# FPGA_Config.net
KiCad netlist of a schematic drawn in Altium Designer
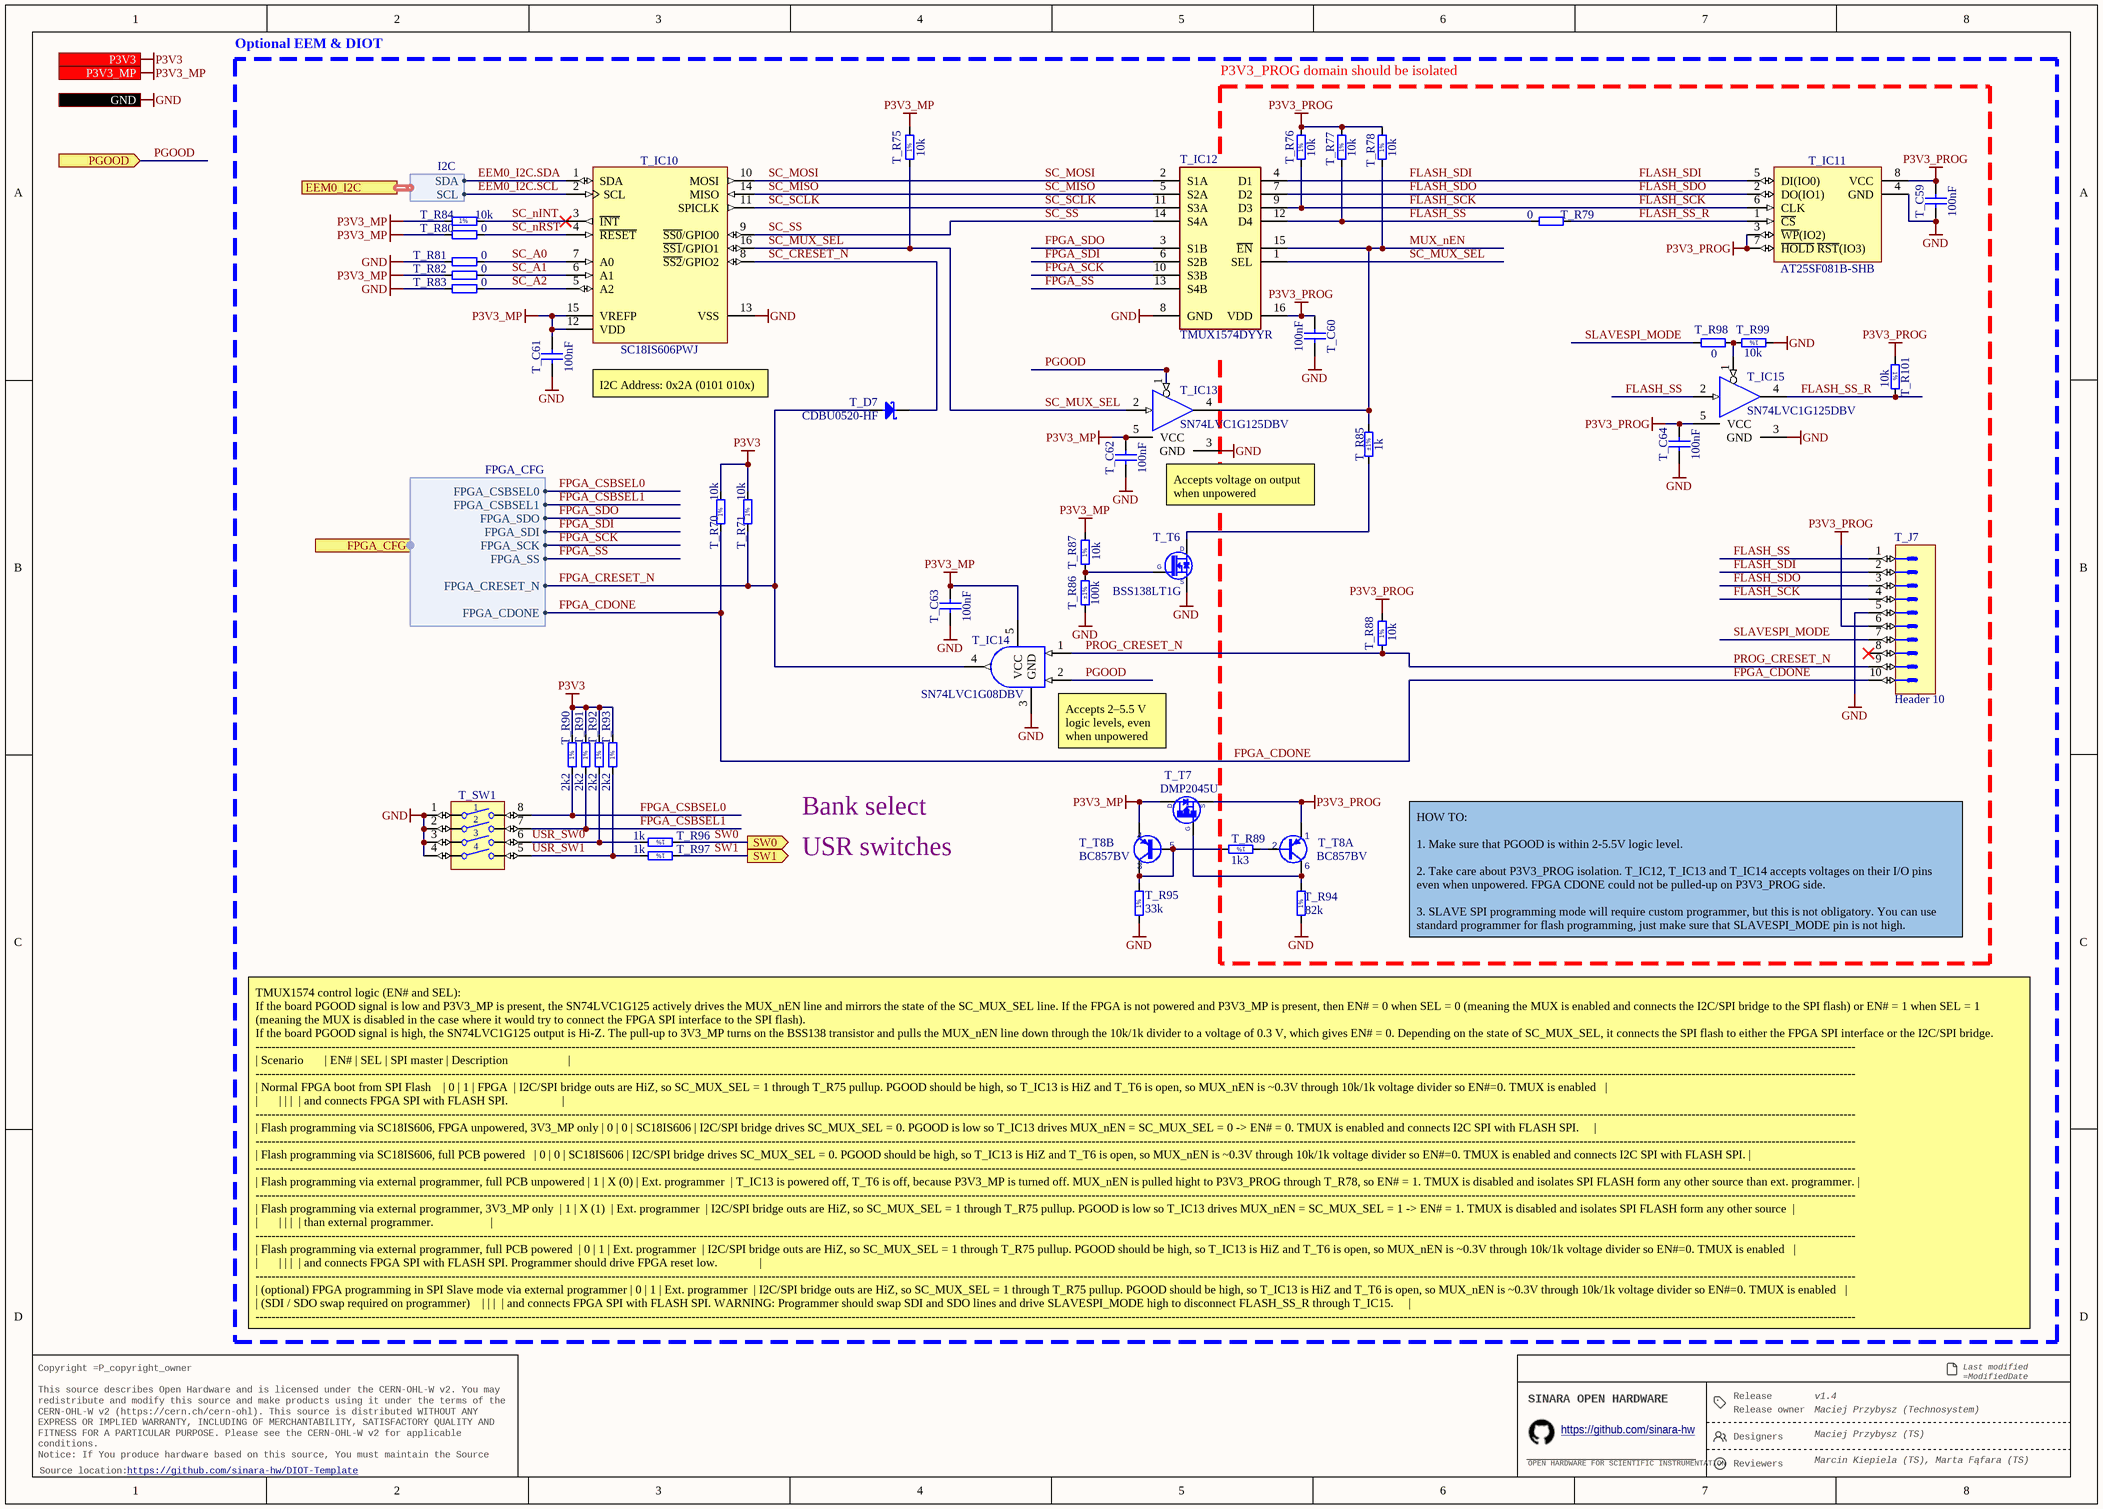
[diagram p0: FPGA_Config.SchDoc]

(export (version "E")
  (design (tool "Eeschema 10.0.6"))
  (components
    (comp (ref "T_C59")
      (value "100nF")
      (footprint "CAPC1005X55N")
      (description "Non-polarised capacitor")
      (fields
        (field (name "PART NUMBER") "CC0402_100NF_50V_10%_X7R")
        (field (name "VOLTAGE") "50V")
        (field (name "AUTHOR") "CERN DEM MR")
      )
      (libsource (lib "Capacitors") (part "Capacitor - non polarized"))
    )
    (comp (ref "T_C60")
      (value "100nF")
      (footprint "CAPC1005X55N")
      (description "Non-polarised capacitor")
      (fields
        (field (name "PART NUMBER") "CC0402_100NF_50V_10%_X7R")
        (field (name "VOLTAGE") "50V")
        (field (name "AUTHOR") "CERN DEM MR")
      )
      (libsource (lib "Capacitors") (part "Capacitor - non polarized"))
    )
    (comp (ref "T_C61")
      (value "100nF")
      (footprint "CAPC1005X55N")
      (description "Non-polarised capacitor")
      (fields
        (field (name "PART NUMBER") "CC0402_100NF_50V_10%_X7R")
        (field (name "VOLTAGE") "50V")
        (field (name "AUTHOR") "CERN DEM MR")
      )
      (libsource (lib "Capacitors") (part "Capacitor - non polarized"))
    )
    (comp (ref "T_C62")
      (value "100nF")
      (footprint "CAPC1005X55N")
      (description "Non-polarised capacitor")
      (fields
        (field (name "PART NUMBER") "CC0402_100NF_50V_10%_X7R")
        (field (name "VOLTAGE") "50V")
        (field (name "AUTHOR") "CERN DEM MR")
      )
      (libsource (lib "Capacitors") (part "Capacitor - non polarized"))
    )
    (comp (ref "T_C63")
      (value "100nF")
      (footprint "CAPC1005X55N")
      (description "Non-polarised capacitor")
      (fields
        (field (name "PART NUMBER") "CC0402_100NF_50V_10%_X7R")
        (field (name "VOLTAGE") "50V")
        (field (name "AUTHOR") "CERN DEM MR")
      )
      (libsource (lib "Capacitors") (part "Capacitor - non polarized"))
    )
    (comp (ref "T_C64")
      (value "100nF")
      (footprint "CAPC1005X55N")
      (description "Non-polarised capacitor")
      (fields
        (field (name "PART NUMBER") "CC0402_100NF_50V_10%_X7R")
        (field (name "VOLTAGE") "50V")
        (field (name "AUTHOR") "CERN DEM MR")
      )
      (libsource (lib "Capacitors") (part "Capacitor - non polarized"))
    )
    (comp (ref "T_D7")
      (value "CDBU0520-HF")
      (footprint "SOD-523F")
      (description "Schottky Diode")
      (fields
        (field (name "VOLTAGE") "20V")
        (field (name "POWER") "500mA")
        (field (name "AUTHOR") "CERN DEM HF")
      )
      (libsource (lib "ICs And Semiconductors") (part "Diode Schottky"))
    )
    (comp (ref "T_IC10")
      (value "SC18IS606PWJ")
      (footprint "SOP65P640X110-16N")
      (description "I2C-bus to SPI bridge")
      (fields (field (name "MANUFACTURER") "NXP SEMICONDUCTORS") (field (name "AUTHOR") "GK"))
      (libsource (lib "ICS-logic") (part "SC18IS606PWJ"))
    )
    (comp (ref "T_IC11")
      (value "AT25SF081B-SHB")
      (footprint "SOIC127P790X216-8N")
      (description "8M-bit Serial Flash Memory with uniform 4KB sectors and Dual/Quad SPI and QPI")
      (fields (field (name "MANUFACTURER") "Renesas") (field (name "AUTHOR") "GK"))
      (libsource (lib "ICS-logic") (part "MEM_AT25SF081B-SHB"))
    )
    (comp (ref "T_IC12")
      (value "TMUX1574DYYR")
      (footprint "SamacSys:SOP50P326X110-16N")
      (description "Integrated Circuit")
      (fields (field (name "MOUSER PART NUMBER") "595-TMUX1574DYYR"))
      (libsource (lib "SamacSys") (part "TMUX1574DYYR"))
    )
    (comp (ref "T_IC13")
      (value "SN74LVC1G125DBV")
      (footprint "SOT95P280X145-5N")
      (description "Single Bus Buffer Gate With 3-State Output")
      (fields (field (name "MANUFACTURER") "TEXAS INSTRUMENTS") (field (name "AUTHOR") "CERN DEM HF"))
      (libsource (lib "ICs And Semiconductors") (part "741G125"))
    )
    (comp (ref "T_IC14")
      (value "SN74LVC1G08DBV")
      (footprint "SOT95P280X145-5N")
      (description "Single 2-Input AND Gate")
      (fields (field (name "MANUFACTURER") "TEXAS INSTRUMENTS") (field (name "AUTHOR") "CERN DEM JLC"))
      (libsource (lib "ICs And Semiconductors") (part "741G08"))
    )
    (comp (ref "T_IC15")
      (value "SN74LVC1G125DBV")
      (footprint "SOT95P280X145-5N")
      (description "Single Bus Buffer Gate With 3-State Output")
      (fields (field (name "MANUFACTURER") "TEXAS INSTRUMENTS") (field (name "AUTHOR") "CERN DEM HF"))
      (libsource (lib "ICs And Semiconductors") (part "741G125"))
    )
    (comp (ref "T_J7")
      (value "Header 10")
      (footprint "HARWIN_M20-9980546")
      (description "Connector 10 Male")
      (fields
        (field (name "PART NUMBER") "HARWIN_M20-9980546")
        (field (name "MANUFACTURER") "HARWIN")
        (field (name "AUTHOR") "CERN DEM MR")
      )
      (libsource (lib "Connectors") (part "Connector 10 Male"))
    )
    (comp (ref "T_R70")
      (value "10k")
      (footprint "RESC1005X40N")
      (description "Resistor - 1%")
      (fields
        (field (name "PART NUMBER") "R0402_10K_1%_0.0625W_100PPM")
        (field (name "POWER") "0.0625W")
        (field (name "AUTHOR") "CERN DEM JLC")
      )
      (libsource (lib "Resistors") (part "Resistor - 1%"))
    )
    (comp (ref "T_R71")
      (value "10k")
      (footprint "RESC1005X40N")
      (description "Resistor - 1%")
      (fields
        (field (name "PART NUMBER") "R0402_10K_1%_0.0625W_100PPM")
        (field (name "POWER") "0.0625W")
        (field (name "AUTHOR") "CERN DEM JLC")
      )
      (libsource (lib "Resistors") (part "Resistor - 1%"))
    )
    (comp (ref "T_R75")
      (value "10k")
      (footprint "RESC1005X40N")
      (description "Resistor - 1%")
      (fields
        (field (name "PART NUMBER") "R0402_10K_1%_0.0625W_100PPM")
        (field (name "POWER") "0.0625W")
        (field (name "AUTHOR") "CERN DEM JLC")
      )
      (libsource (lib "Resistors") (part "Resistor - 1%"))
    )
    (comp (ref "T_R76")
      (value "10k")
      (footprint "RESC1005X40N")
      (description "Resistor - 1%")
      (fields
        (field (name "PART NUMBER") "R0402_10K_1%_0.0625W_100PPM")
        (field (name "POWER") "0.0625W")
        (field (name "AUTHOR") "CERN DEM JLC")
      )
      (libsource (lib "Resistors") (part "Resistor - 1%"))
    )
    (comp (ref "T_R77")
      (value "10k")
      (footprint "RESC1005X40N")
      (description "Resistor - 1%")
      (fields
        (field (name "PART NUMBER") "R0402_10K_1%_0.0625W_100PPM")
        (field (name "POWER") "0.0625W")
        (field (name "AUTHOR") "CERN DEM JLC")
      )
      (libsource (lib "Resistors") (part "Resistor - 1%"))
    )
    (comp (ref "T_R78")
      (value "10k")
      (footprint "RESC1005X40N")
      (description "Resistor - 1%")
      (fields
        (field (name "PART NUMBER") "R0402_10K_1%_0.0625W_100PPM")
        (field (name "POWER") "0.0625W")
        (field (name "AUTHOR") "CERN DEM JLC")
      )
      (libsource (lib "Resistors") (part "Resistor - 1%"))
    )
    (comp (ref "T_R79")
      (value "0")
      (footprint "RESC1005X40N")
      (description "Resistor")
      (fields
        (field (name "PART NUMBER") "R0402_0R_JUMPER")
        (field (name "MANUFACTURER") "GENERIC")
        (field (name "AUTHOR") "CERN DEM JLC")
      )
      (libsource (lib "Resistors") (part "Resistor"))
    )
    (comp (ref "T_R80")
      (value "0")
      (footprint "RESC1005X40N")
      (description "Resistor")
      (fields
        (field (name "PART NUMBER") "R0402_0R_JUMPER")
        (field (name "MANUFACTURER") "GENERIC")
        (field (name "AUTHOR") "CERN DEM JLC")
      )
      (libsource (lib "Resistors") (part "Resistor"))
    )
    (comp (ref "T_R81")
      (value "0")
      (footprint "RESC1005X40N")
      (description "Resistor")
      (fields
        (field (name "PART NUMBER") "R0402_0R_JUMPER")
        (field (name "MANUFACTURER") "GENERIC")
        (field (name "AUTHOR") "CERN DEM JLC")
      )
      (libsource (lib "Resistors") (part "Resistor"))
    )
    (comp (ref "T_R82")
      (value "0")
      (footprint "RESC1005X40N")
      (description "Resistor")
      (fields
        (field (name "PART NUMBER") "R0402_0R_JUMPER")
        (field (name "MANUFACTURER") "GENERIC")
        (field (name "AUTHOR") "CERN DEM JLC")
      )
      (libsource (lib "Resistors") (part "Resistor"))
    )
    (comp (ref "T_R83")
      (value "0")
      (footprint "RESC1005X40N")
      (description "Resistor")
      (fields
        (field (name "PART NUMBER") "R0402_0R_JUMPER")
        (field (name "MANUFACTURER") "GENERIC")
        (field (name "AUTHOR") "CERN DEM JLC")
      )
      (libsource (lib "Resistors") (part "Resistor"))
    )
    (comp (ref "T_R84")
      (value "10k")
      (footprint "RESC1005X40N")
      (description "Resistor - 1%")
      (fields
        (field (name "PART NUMBER") "R0402_10K_1%_0.0625W_100PPM")
        (field (name "POWER") "0.0625W")
        (field (name "AUTHOR") "CERN DEM JLC")
      )
      (libsource (lib "Resistors") (part "Resistor - 1%"))
    )
    (comp (ref "T_R85")
      (value "1k")
      (footprint "RESC1005X40N")
      (description "Resistor - 1%")
      (fields
        (field (name "TOLERANCE") "±1%")
        (field (name "PART NUMBER") "R0402_1K_1%_0.0625W_100PPM")
        (field (name "POWER") "0.0625W")
        (field (name "AUTHOR") "CERN DEM JLC")
      )
      (libsource (lib "Resistors") (part "Resistor - 1%"))
    )
    (comp (ref "T_R86")
      (value "100k")
      (footprint "RESC1005X40N")
      (description "Resistor - 1%")
      (fields
        (field (name "TOLERANCE") "±1%")
        (field (name "PART NUMBER") "R0402_100K_1%_0.0625W_100PPM")
        (field (name "POWER") "0.0625W")
        (field (name "AUTHOR") "CERN DEM JLC")
      )
      (libsource (lib "Resistors") (part "Resistor - 1%"))
    )
    (comp (ref "T_R87")
      (value "10k")
      (footprint "RESC1005X40N")
      (description "Resistor - 1%")
      (fields
        (field (name "PART NUMBER") "R0402_10K_1%_0.0625W_100PPM")
        (field (name "POWER") "0.0625W")
        (field (name "AUTHOR") "CERN DEM JLC")
      )
      (libsource (lib "Resistors") (part "Resistor - 1%"))
    )
    (comp (ref "T_R88")
      (value "10k")
      (footprint "RESC1005X40N")
      (description "Resistor - 1%")
      (fields
        (field (name "PART NUMBER") "R0402_10K_1%_0.0625W_100PPM")
        (field (name "POWER") "0.0625W")
        (field (name "AUTHOR") "CERN DEM JLC")
      )
      (libsource (lib "Resistors") (part "Resistor - 1%"))
    )
    (comp (ref "T_R89")
      (value "1k3")
      (footprint "RESC1608X55N")
      (description "Resistor - 1%")
      (fields
        (field (name "PART NUMBER") "R0603_1K3_1%_0.1W_100PPM")
        (field (name "POWER") "0.1W")
        (field (name "AUTHOR") "CERN DEM JLC")
      )
      (libsource (lib "Resistors") (part "Resistor - 1%"))
    )
    (comp (ref "T_R90")
      (value "2k2")
      (footprint "RESC1005X40N")
      (description "Resistor - 1%")
      (fields
        (field (name "PART NUMBER") "R0402_2K2_1%_0.0625W_100PPM")
        (field (name "POWER") "0.0625W")
        (field (name "AUTHOR") "CERN DEM JLC")
      )
      (libsource (lib "Resistors") (part "Resistor - 1%"))
    )
    (comp (ref "T_R91")
      (value "2k2")
      (footprint "RESC1005X40N")
      (description "Resistor - 1%")
      (fields
        (field (name "PART NUMBER") "R0402_2K2_1%_0.0625W_100PPM")
        (field (name "POWER") "0.0625W")
        (field (name "AUTHOR") "CERN DEM JLC")
      )
      (libsource (lib "Resistors") (part "Resistor - 1%"))
    )
    (comp (ref "T_R92")
      (value "2k2")
      (footprint "RESC1005X40N")
      (description "Resistor - 1%")
      (fields
        (field (name "PART NUMBER") "R0402_2K2_1%_0.0625W_100PPM")
        (field (name "POWER") "0.0625W")
        (field (name "AUTHOR") "CERN DEM JLC")
      )
      (libsource (lib "Resistors") (part "Resistor - 1%"))
    )
    (comp (ref "T_R93")
      (value "2k2")
      (footprint "RESC1005X40N")
      (description "Resistor - 1%")
      (fields
        (field (name "PART NUMBER") "R0402_2K2_1%_0.0625W_100PPM")
        (field (name "POWER") "0.0625W")
        (field (name "AUTHOR") "CERN DEM JLC")
      )
      (libsource (lib "Resistors") (part "Resistor - 1%"))
    )
    (comp (ref "T_R94")
      (value "82k")
      (footprint "RESC1608X55N")
      (description "Resistor - 1%")
      (fields
        (field (name "PART NUMBER") "R0603_82K_1%_0.1W_100PPM")
        (field (name "POWER") "0.1W")
        (field (name "AUTHOR") "CERN DEM JLC")
      )
      (libsource (lib "Resistors") (part "Resistor - 1%"))
    )
    (comp (ref "T_R95")
      (value "33k")
      (footprint "RESC1005X40N")
      (description "Resistor - 1%")
      (fields
        (field (name "PART NUMBER") "R0402_33K_1%_0.0625W_100PPM")
        (field (name "POWER") "0.0625W")
        (field (name "AUTHOR") "CERN DEM JLC")
      )
      (libsource (lib "Resistors") (part "Resistor - 1%"))
    )
    (comp (ref "T_R96")
      (value "1k")
      (footprint "RESC1005X40N")
      (description "Resistor - 1%")
      (fields
        (field (name "PART NUMBER") "R0402_1K_1%_0.0625W_100PPM")
        (field (name "POWER") "0.0625W")
        (field (name "AUTHOR") "CERN DEM JLC")
      )
      (libsource (lib "Resistors") (part "Resistor - 1%"))
    )
    (comp (ref "T_R97")
      (value "1k")
      (footprint "RESC1005X40N")
      (description "Resistor - 1%")
      (fields
        (field (name "PART NUMBER") "R0402_1K_1%_0.0625W_100PPM")
        (field (name "POWER") "0.0625W")
        (field (name "AUTHOR") "CERN DEM JLC")
      )
      (libsource (lib "Resistors") (part "Resistor - 1%"))
    )
    (comp (ref "T_R98")
      (value "0")
      (footprint "RESC1005X40N")
      (description "Resistor")
      (fields
        (field (name "PART NUMBER") "R0402_0R_JUMPER")
        (field (name "MANUFACTURER") "GENERIC")
        (field (name "AUTHOR") "CERN DEM JLC")
      )
      (libsource (lib "Resistors") (part "Resistor"))
    )
    (comp (ref "T_R99")
      (value "10k")
      (footprint "RESC1005X40N")
      (description "Resistor - 1%")
      (fields
        (field (name "PART NUMBER") "R0402_10K_1%_0.0625W_100PPM")
        (field (name "POWER") "0.0625W")
        (field (name "AUTHOR") "CERN DEM JLC")
      )
      (libsource (lib "Resistors") (part "Resistor - 1%"))
    )
    (comp (ref "T_R101")
      (value "10k")
      (footprint "RESC1005X40N")
      (description "Resistor - 1%")
      (fields
        (field (name "PART NUMBER") "R0402_10K_1%_0.0625W_100PPM")
        (field (name "POWER") "0.0625W")
        (field (name "AUTHOR") "CERN DEM JLC")
      )
      (libsource (lib "Resistors") (part "Resistor - 1%"))
    )
    (comp (ref "T_SW1")
      (value "Switch")
      (footprint "SW_TYCO_1571983-4")
      (description "4 Ways SPST DIP Switch")
      (fields
        (field (name "PART NUMBER") "SW_TYCO_1571983-4")
        (field (name "MANUFACTURER") "TYCO")
        (field (name "AUTHOR") "CERN DEM JLC")
      )
      (libsource (lib "Eletro-mechanical") (part "SW 4x SPST DIP Switch"))
    )
    (comp (ref "T_T6")
      (value "BSS138LT1G")
      (footprint "SOT95P240X110-3N")
      (description "N-CHANNEL MOSFET WITH DIODE")
      (fields
        (field (name "MANUFACTURER") "ON SEMICONDUCTOR")
        (field (name "MANUFACTURER PART NUMBER") "BSS138L")
        (field (name "AUTHOR") "CERN DEM JLC")
      )
      (libsource (lib "ICs And Semiconductors") (part "N-MOSFET-D 1G 2S 3D"))
    )
    (comp (ref "T_T7")
      (value "DMP2045U")
      (footprint "SOT95P240X110-3N")
      (description "P-CHANNEL MOSFET WITH DIODE")
      (fields (field (name "MANUFACTURER") "DIODES INCORPORATED") (field (name "AUTHOR") "CERN DEM HF"))
      (libsource (lib "ICs And Semiconductors") (part "P-MOSFET-D 1G 2S 3D"))
    )
    (comp (ref "T_T8")
      (value "BC857BV")
      (footprint "SOTFL50P160X60-6N")
      (description "45V, 100mA PNP General Purpose Double Transistor")
      (fields (field (name "MANUFACTURER") "NXP SEMICONDUCTORS") (field (name "AUTHOR") "CERN DEM JLC"))
      (libsource (lib "ICs And Semiconductors") (part "BC857BV"))
    )
  )
  (nets
    (net (code "3") (name "/EEM0_I2C.SCL") (class "Default")
      (node (ref "T_IC10") (pin "2") (pinfunction "SCL_2") (pintype "input"))
    )
    (net (code "4") (name "/EEM0_I2C.SDA") (class "Default")
      (node (ref "T_IC10") (pin "1") (pinfunction "SDA_1") (pintype "bidirectional"))
    )
    (net (code "5") (name "/FLASH_SCK") (class "Default")
      (node (ref "T_IC11") (pin "6") (pinfunction "CLK_6") (pintype "input"))
      (node (ref "T_IC12") (pin "9") (pinfunction "D3_9") (pintype "passive"))
      (node (ref "T_J7") (pin "4") (pinfunction "4_4") (pintype "bidirectional"))
      (node (ref "T_R76") (pin "1") (pinfunction "1_1") (pintype "passive"))
    )
    (net (code "6") (name "/FLASH_SDI") (class "Default")
      (node (ref "T_IC11") (pin "5") (pinfunction "DI(IO0)_5") (pintype "bidirectional"))
      (node (ref "T_IC12") (pin "4") (pinfunction "D1_4") (pintype "passive"))
      (node (ref "T_J7") (pin "2") (pinfunction "2_2") (pintype "bidirectional"))
    )
    (net (code "7") (name "/FLASH_SDO") (class "Default")
      (node (ref "T_IC11") (pin "2") (pinfunction "DO(IO1)_2") (pintype "bidirectional"))
      (node (ref "T_IC12") (pin "7") (pinfunction "D2_7") (pintype "passive"))
      (node (ref "T_J7") (pin "3") (pinfunction "3_3") (pintype "bidirectional"))
    )
    (net (code "8") (name "/FLASH_SS") (class "Default")
      (node (ref "T_IC12") (pin "12") (pinfunction "D4_12") (pintype "passive"))
      (node (ref "T_IC15") (pin "2") (pinfunction "IN_2") (pintype "input"))
      (node (ref "T_J7") (pin "1") (pinfunction "1_1") (pintype "bidirectional"))
      (node (ref "T_R77") (pin "1") (pinfunction "1_1") (pintype "passive"))
      (node (ref "T_R79") (pin "1") (pinfunction "1_1") (pintype "passive"))
    )
    (net (code "9") (name "/FLASH_SS_R") (class "Default")
      (node (ref "T_IC11") (pin "1") (pinfunction "~{CS}_1") (pintype "input"))
      (node (ref "T_IC15") (pin "4") (pinfunction "OUT_4") (pintype "tri_state"))
      (node (ref "T_R101") (pin "2") (pinfunction "2_2") (pintype "passive"))
      (node (ref "T_R79") (pin "2") (pinfunction "2_2") (pintype "passive"))
    )
    (net (code "10") (name "/FPGA_CDONE") (class "Default")
      (node (ref "T_J7") (pin "10") (pinfunction "10_10") (pintype "bidirectional"))
      (node (ref "T_R70") (pin "1") (pinfunction "1_1") (pintype "passive"))
    )
    (net (code "11") (name "/FPGA_CRESET_N") (class "Default")
      (node (ref "T_D7") (pin "2") (pinfunction "A_2") (pintype "passive"))
      (node (ref "T_IC14") (pin "4") (pinfunction "Y_4") (pintype "output"))
      (node (ref "T_R71") (pin "1") (pinfunction "1_1") (pintype "passive"))
    )
    (net (code "12") (name "/FPGA_CSBSEL0") (class "Default")
      (node (ref "T_R90") (pin "1") (pinfunction "1_1") (pintype "passive"))
      (node (ref "T_SW1") (pin "8") (pinfunction "8_8") (pintype "bidirectional"))
    )
    (net (code "13") (name "/FPGA_CSBSEL1") (class "Default")
      (node (ref "T_R91") (pin "1") (pinfunction "1_1") (pintype "passive"))
      (node (ref "T_SW1") (pin "7") (pinfunction "7_7") (pintype "bidirectional"))
    )
    (net (code "14") (name "/FPGA_SCK") (class "Default")
      (node (ref "T_IC12") (pin "10") (pinfunction "S3B_10") (pintype "passive"))
    )
    (net (code "15") (name "/FPGA_SDI") (class "Default")
      (node (ref "T_IC12") (pin "6") (pinfunction "S2B_6") (pintype "passive"))
    )
    (net (code "16") (name "/FPGA_SDO") (class "Default")
      (node (ref "T_IC12") (pin "3") (pinfunction "S1B_3") (pintype "passive"))
    )
    (net (code "17") (name "/FPGA_SS") (class "Default")
      (node (ref "T_IC12") (pin "13") (pinfunction "S4B_13") (pintype "passive"))
    )
    (net (code "18") (name "/MUX_nEN") (class "Default")
      (node (ref "T_IC12") (pin "15") (pinfunction "~{EN}_15") (pintype "passive"))
      (node (ref "T_IC13") (pin "4") (pinfunction "OUT_4") (pintype "tri_state"))
      (node (ref "T_R78") (pin "1") (pinfunction "1_1") (pintype "passive"))
      (node (ref "T_R85") (pin "2") (pinfunction "2_2") (pintype "passive"))
    )
    (net (code "19") (name "/PGOOD") (class "Default")
      (node (ref "T_IC13") (pin "1") (pinfunction "~{G}_1") (pintype "input"))
      (node (ref "T_IC14") (pin "2") (pinfunction "B_2") (pintype "input"))
    )
    (net (code "20") (name "/PROG_CRESET_N") (class "Default")
      (node (ref "T_IC14") (pin "1") (pinfunction "A_1") (pintype "input"))
      (node (ref "T_J7") (pin "9") (pinfunction "9_9") (pintype "bidirectional"))
      (node (ref "T_R88") (pin "1") (pinfunction "1_1") (pintype "passive"))
    )
    (net (code "21") (name "/SC_A0") (class "Default")
      (node (ref "T_IC10") (pin "7") (pinfunction "A0_7") (pintype "input"))
      (node (ref "T_R81") (pin "1") (pinfunction "1_1") (pintype "passive"))
    )
    (net (code "22") (name "/SC_A1") (class "Default")
      (node (ref "T_IC10") (pin "6") (pinfunction "A1_6") (pintype "input"))
      (node (ref "T_R82") (pin "1") (pinfunction "1_1") (pintype "passive"))
    )
    (net (code "23") (name "/SC_A2") (class "Default")
      (node (ref "T_IC10") (pin "5") (pinfunction "A2_5") (pintype "bidirectional"))
      (node (ref "T_R83") (pin "1") (pinfunction "1_1") (pintype "passive"))
    )
    (net (code "24") (name "/SC_CRESET_N") (class "Default")
      (node (ref "T_D7") (pin "1") (pinfunction "C_1") (pintype "passive"))
      (node (ref "T_IC10") (pin "8") (pinfunction "~{SS2}/GPIO2_8") (pintype "bidirectional"))
    )
    (net (code "25") (name "/SC_MISO") (class "Default")
      (node (ref "T_IC10") (pin "14") (pinfunction "MISO_14") (pintype "input"))
      (node (ref "T_IC12") (pin "5") (pinfunction "S2A_5") (pintype "passive"))
    )
    (net (code "26") (name "/SC_MOSI") (class "Default")
      (node (ref "T_IC10") (pin "10") (pinfunction "MOSI_10") (pintype "output"))
      (node (ref "T_IC12") (pin "2") (pinfunction "S1A_2") (pintype "passive"))
    )
    (net (code "27") (name "/SC_MUX_SEL") (class "Default")
      (node (ref "T_IC10") (pin "16") (pinfunction "~{SS1}/GPIO1_16") (pintype "bidirectional"))
      (node (ref "T_IC12") (pin "1") (pinfunction "SEL_1") (pintype "passive"))
      (node (ref "T_IC13") (pin "2") (pinfunction "IN_2") (pintype "input"))
      (node (ref "T_R75") (pin "1") (pinfunction "1_1") (pintype "passive"))
    )
    (net (code "28") (name "/SC_SCLK") (class "Default")
      (node (ref "T_IC10") (pin "11") (pinfunction "SPICLK_11") (pintype "output"))
      (node (ref "T_IC12") (pin "11") (pinfunction "S3A_11") (pintype "passive"))
    )
    (net (code "29") (name "/SC_SS") (class "Default")
      (node (ref "T_IC10") (pin "9") (pinfunction "~{SS0}/GPIO0_9") (pintype "bidirectional"))
      (node (ref "T_IC12") (pin "14") (pinfunction "S4A_14") (pintype "passive"))
    )
    (net (code "30") (name "/SC_nINT") (class "Default")
      (node (ref "T_IC10") (pin "3") (pinfunction "~{INT}_3") (pintype "output"))
      (node (ref "T_R84") (pin "2") (pinfunction "2_2") (pintype "passive"))
    )
    (net (code "31") (name "/SC_nRST") (class "Default")
      (node (ref "T_IC10") (pin "4") (pinfunction "~{RESET}_4") (pintype "input"))
      (node (ref "T_R80") (pin "1") (pinfunction "1_1") (pintype "passive"))
    )
    (net (code "32") (name "/SLAVESPI_MODE") (class "Default")
      (node (ref "T_J7") (pin "7") (pinfunction "7_7") (pintype "bidirectional"))
      (node (ref "T_R98") (pin "1") (pinfunction "1_1") (pintype "passive"))
    )
    (net (code "33") (name "/SW0") (class "Default")
      (node (ref "T_R96") (pin "1") (pinfunction "1_1") (pintype "passive"))
    )
    (net (code "34") (name "/SW1") (class "Default")
      (node (ref "T_R97") (pin "1") (pinfunction "1_1") (pintype "passive"))
    )
    (net (code "35") (name "/USR_SW0") (class "Default")
      (node (ref "T_R92") (pin "1") (pinfunction "1_1") (pintype "passive"))
      (node (ref "T_R96") (pin "2") (pinfunction "2_2") (pintype "passive"))
      (node (ref "T_SW1") (pin "6") (pinfunction "6_6") (pintype "bidirectional"))
    )
    (net (code "36") (name "/USR_SW1") (class "Default")
      (node (ref "T_R93") (pin "1") (pinfunction "1_1") (pintype "passive"))
      (node (ref "T_R97") (pin "2") (pinfunction "2_2") (pintype "passive"))
      (node (ref "T_SW1") (pin "5") (pinfunction "5_5") (pintype "bidirectional"))
    )
    (net (code "39") (name "GND") (class "Default")
      (node (ref "T_C59") (pin "1") (pinfunction "1_1") (pintype "passive"))
      (node (ref "T_C60") (pin "1") (pinfunction "1_1") (pintype "passive"))
      (node (ref "T_C61") (pin "1") (pinfunction "1_1") (pintype "passive"))
      (node (ref "T_C62") (pin "1") (pinfunction "1_1") (pintype "passive"))
      (node (ref "T_C63") (pin "1") (pinfunction "1_1") (pintype "passive"))
      (node (ref "T_C64") (pin "1") (pinfunction "1_1") (pintype "passive"))
      (node (ref "T_IC10") (pin "13") (pinfunction "VSS_13") (pintype "power_in"))
      (node (ref "T_IC11") (pin "4") (pinfunction "GND_4") (pintype "power_in"))
      (node (ref "T_IC12") (pin "8") (pinfunction "GND_8") (pintype "passive"))
      (node (ref "T_IC13") (pin "3") (pinfunction "GND_3") (pintype "power_in"))
      (node (ref "T_IC14") (pin "3") (pinfunction "GND_3") (pintype "power_in"))
      (node (ref "T_IC15") (pin "3") (pinfunction "GND_3") (pintype "power_in"))
      (node (ref "T_J7") (pin "5") (pinfunction "5_5") (pintype "bidirectional"))
      (node (ref "T_R81") (pin "2") (pinfunction "2_2") (pintype "passive"))
      (node (ref "T_R83") (pin "2") (pinfunction "2_2") (pintype "passive"))
      (node (ref "T_R86") (pin "2") (pinfunction "2_2") (pintype "passive"))
      (node (ref "T_R94") (pin "1") (pinfunction "1_1") (pintype "passive"))
      (node (ref "T_R95") (pin "1") (pinfunction "1_1") (pintype "passive"))
      (node (ref "T_R99") (pin "1") (pinfunction "1_1") (pintype "passive"))
      (node (ref "T_SW1") (pin "1") (pinfunction "1_1") (pintype "bidirectional"))
      (node (ref "T_SW1") (pin "2") (pinfunction "2_2") (pintype "bidirectional"))
      (node (ref "T_SW1") (pin "3") (pinfunction "3_3") (pintype "bidirectional"))
      (node (ref "T_SW1") (pin "4") (pinfunction "4_4") (pintype "bidirectional"))
      (node (ref "T_T6") (pin "2") (pinfunction "S_2") (pintype "passive"))
    )
    (net (code "40") (name "Net-(T_IC15-~{G})") (class "Default")
      (node (ref "T_IC15") (pin "1") (pinfunction "~{G}_1") (pintype "input"))
      (node (ref "T_R98") (pin "2") (pinfunction "2_2") (pintype "passive"))
      (node (ref "T_R99") (pin "2") (pinfunction "2_2") (pintype "passive"))
    )
    (net (code "41") (name "Net-(T_T6-D)") (class "Default")
      (node (ref "T_R85") (pin "1") (pinfunction "1_1") (pintype "passive"))
      (node (ref "T_T6") (pin "3") (pinfunction "D_3") (pintype "passive"))
    )
    (net (code "42") (name "Net-(T_T6-G)") (class "Default")
      (node (ref "T_R86") (pin "1") (pinfunction "1_1") (pintype "passive"))
      (node (ref "T_R87") (pin "1") (pinfunction "1_1") (pintype "passive"))
      (node (ref "T_T6") (pin "1") (pinfunction "G_1") (pintype "passive"))
    )
    (net (code "43") (name "Net-(T_T7-G)") (class "Default")
      (node (ref "T_R94") (pin "2") (pinfunction "2_2") (pintype "passive"))
      (node (ref "T_T7") (pin "1") (pinfunction "G_1") (pintype "passive"))
      (node (ref "T_T8") (pin "6") (pinfunction "C_6") (pintype "passive"))
    )
    (net (code "44") (name "Net-(T_T8A-B)") (class "Default")
      (node (ref "T_R89") (pin "1") (pinfunction "1_1") (pintype "passive"))
      (node (ref "T_T8") (pin "2") (pinfunction "B_2") (pintype "passive"))
    )
    (net (code "45") (name "Net-(T_T8B-B)") (class "Default")
      (node (ref "T_R89") (pin "2") (pinfunction "2_2") (pintype "passive"))
      (node (ref "T_R95") (pin "2") (pinfunction "2_2") (pintype "passive"))
      (node (ref "T_T8") (pin "3") (pinfunction "C_3") (pintype "passive"))
      (node (ref "T_T8") (pin "5") (pinfunction "B_5") (pintype "passive"))
    )
    (net (code "46") (name "P3V3") (class "Default")
      (node (ref "T_R70") (pin "2") (pinfunction "2_2") (pintype "passive"))
      (node (ref "T_R71") (pin "2") (pinfunction "2_2") (pintype "passive"))
      (node (ref "T_R90") (pin "2") (pinfunction "2_2") (pintype "passive"))
      (node (ref "T_R91") (pin "2") (pinfunction "2_2") (pintype "passive"))
      (node (ref "T_R92") (pin "2") (pinfunction "2_2") (pintype "passive"))
      (node (ref "T_R93") (pin "2") (pinfunction "2_2") (pintype "passive"))
    )
    (net (code "47") (name "P3V3_MP") (class "Default")
      (node (ref "T_C61") (pin "2") (pinfunction "2_2") (pintype "passive"))
      (node (ref "T_C62") (pin "2") (pinfunction "2_2") (pintype "passive"))
      (node (ref "T_C63") (pin "2") (pinfunction "2_2") (pintype "passive"))
      (node (ref "T_IC10") (pin "12") (pinfunction "VDD_12") (pintype "power_in"))
      (node (ref "T_IC10") (pin "15") (pinfunction "VREFP_15") (pintype "power_in"))
      (node (ref "T_IC13") (pin "5") (pinfunction "VCC_5") (pintype "power_in"))
      (node (ref "T_IC14") (pin "5") (pinfunction "VCC_5") (pintype "power_in"))
      (node (ref "T_R75") (pin "2") (pinfunction "2_2") (pintype "passive"))
      (node (ref "T_R80") (pin "2") (pinfunction "2_2") (pintype "passive"))
      (node (ref "T_R82") (pin "2") (pinfunction "2_2") (pintype "passive"))
      (node (ref "T_R84") (pin "1") (pinfunction "1_1") (pintype "passive"))
      (node (ref "T_R87") (pin "2") (pinfunction "2_2") (pintype "passive"))
      (node (ref "T_T7") (pin "3") (pinfunction "D_3") (pintype "passive"))
      (node (ref "T_T8") (pin "4") (pinfunction "E_4") (pintype "passive"))
    )
    (net (code "48") (name "P3V3_PROG") (class "Default")
      (node (ref "T_C59") (pin "2") (pinfunction "2_2") (pintype "passive"))
      (node (ref "T_C60") (pin "2") (pinfunction "2_2") (pintype "passive"))
      (node (ref "T_C64") (pin "2") (pinfunction "2_2") (pintype "passive"))
      (node (ref "T_IC11") (pin "3") (pinfunction "~{WP}(IO2)_3") (pintype "bidirectional"))
      (node (ref "T_IC11") (pin "7") (pinfunction "~{HOLD}_~{RST}(IO3)_7") (pintype "bidirectional"))
      (node (ref "T_IC11") (pin "8") (pinfunction "VCC_8") (pintype "power_in"))
      (node (ref "T_IC12") (pin "16") (pinfunction "VDD_16") (pintype "passive"))
      (node (ref "T_IC15") (pin "5") (pinfunction "VCC_5") (pintype "power_in"))
      (node (ref "T_J7") (pin "6") (pinfunction "6_6") (pintype "bidirectional"))
      (node (ref "T_R101") (pin "1") (pinfunction "1_1") (pintype "passive"))
      (node (ref "T_R76") (pin "2") (pinfunction "2_2") (pintype "passive"))
      (node (ref "T_R77") (pin "2") (pinfunction "2_2") (pintype "passive"))
      (node (ref "T_R78") (pin "2") (pinfunction "2_2") (pintype "passive"))
      (node (ref "T_R88") (pin "2") (pinfunction "2_2") (pintype "passive"))
      (node (ref "T_T7") (pin "2") (pinfunction "S_2") (pintype "passive"))
      (node (ref "T_T8") (pin "1") (pinfunction "E_1") (pintype "passive"))
    )
    (net (code "49") (name "unconnected-(T_J7-Pad8)") (class "Default")
      (node (ref "T_J7") (pin "8") (pinfunction "8_8") (pintype "bidirectional+no_connect"))
    )
  )
)
